# SIM7600G-H_PWR_CTRL.net
KiCad netlist of a schematic drawn in Altium Designer
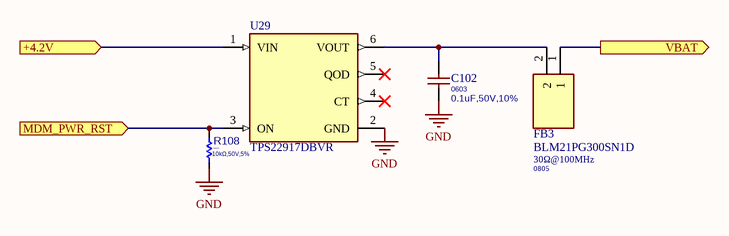
[diagram p0: SIM7600G-H_PWR_CTRL.SchDoc]

(export (version "E")
  (design (tool "Eeschema 10.0.6"))
  (components
    (comp (ref "C102")
      (value "0.1uF,50V,10%")
      (footprint "C0603")
      (description "CAP CER 0.1UF 50V X7R 0603")
      (fields
        (field (name "MANUFACTURER") "Murata Electronics")
        (field (name "MPN") "GCM188R71H104KA57J")
        (field (name "PACKAGE") "0603")
      )
      (libsource (lib "RCL") (part "GCM188R71H104KA57J"))
    )
    (comp (ref "FB3")
      (value "BLM21PG300SN1D")
      (footprint "BEADC2012X105N")
      (description "Ferrite Bead")
      (fields
        (field (name "MANUFACTURER") "Murata Electronics")
        (field (name "ALTIUM_VALUE") "30Ω@100MHz")
        (field (name "PACKAGE") "0805")
      )
      (libsource (lib "RCL") (part "BLM21PG300SN1D"))
    )
    (comp (ref "R108")
      (value "10kΩ,50V,5%")
      (footprint "R0402")
      (description "62.5mW Thick Film Resistors 50V ±100ppm/℃ ±5% 10kΩ 0402 Chip Resistor - Surface Mount ROHS")
      (fields
        (field (name "MANUFACTURER") "YAGEO")
        (field (name "MPN") "RC0402JR-0710KL")
        (field (name "PACKAGE") "0402")
      )
      (libsource (lib "RCL") (part "RC0402JR-0710KL"))
    )
    (comp (ref "U29")
      (value "TPS22917DBVR")
      (footprint "SOT95P280X145-6N")
      (description "5.5-V, 2-A, 80-mÎ© , 10-nA leakage load switch adj. rise time and adj output discharge")
      (fields (field (name "MF") "Texas Instruments"))
      (libsource (lib "IC") (part "TPS22917DBVR"))
    )
  )
  (nets
    (net (code "1") (name "/+4.2V") (class "Default")
      (node (ref "U29") (pin "1") (pinfunction "VIN_1") (pintype "input"))
    )
    (net (code "2") (name "/MDM_PWR_RST") (class "Default")
      (node (ref "R108") (pin "2") (pinfunction "2_2") (pintype "passive"))
      (node (ref "U29") (pin "3") (pinfunction "ON_3") (pintype "input"))
    )
    (net (code "3") (name "/VBAT") (class "Default")
      (node (ref "FB3") (pin "1") (pinfunction "1_1") (pintype "passive"))
    )
    (net (code "4") (name "GND") (class "Default")
      (node (ref "C102") (pin "1") (pinfunction "1_1") (pintype "passive"))
      (node (ref "R108") (pin "1") (pinfunction "1_1") (pintype "passive"))
      (node (ref "U29") (pin "2") (pinfunction "GND_2") (pintype "power_in"))
    )
    (net (code "5") (name "Net-(U29-VOUT)") (class "Default")
      (node (ref "C102") (pin "2") (pinfunction "2_2") (pintype "passive"))
      (node (ref "FB3") (pin "2") (pinfunction "2_2") (pintype "passive"))
      (node (ref "U29") (pin "6") (pinfunction "VOUT_6") (pintype "output"))
    )
    (net (code "6") (name "unconnected-(U29-CT-Pad4)") (class "Default")
      (node (ref "U29") (pin "4") (pinfunction "CT_4") (pintype "output+no_connect"))
    )
    (net (code "7") (name "unconnected-(U29-QOD-Pad5)") (class "Default")
      (node (ref "U29") (pin "5") (pinfunction "QOD_5") (pintype "output+no_connect"))
    )
  )
)
